# stm32g474.net
KiCad netlist of a schematic drawn in Altium Designer
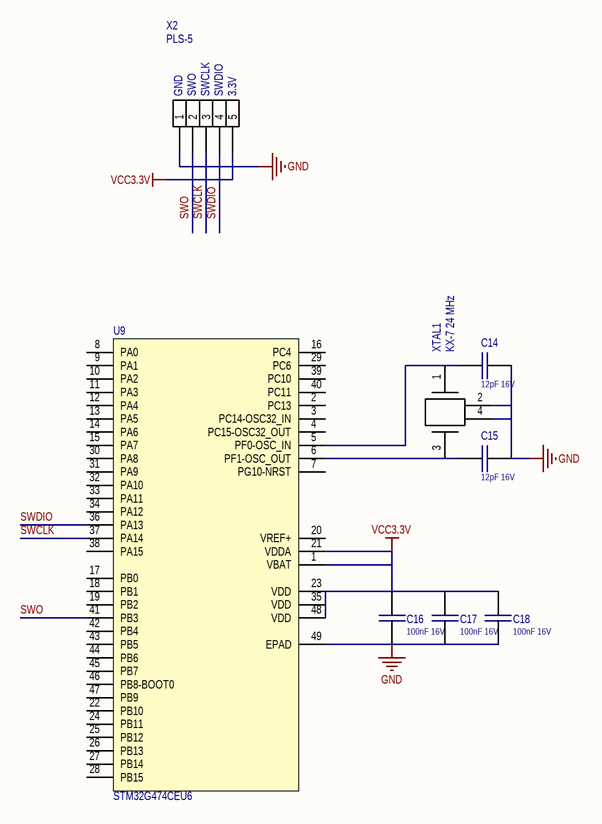
[diagram p0: stm32g474.schdoc]

(export (version "E")
  (design (tool "Eeschema 10.0.6"))
  (components
    (comp (ref "C14")
      (value "12pF 16V")
      (footprint "C_0603")
      (description "Capacitor")
      (libsource (lib "AX_Altium_v2.3") (part "C0603"))
    )
    (comp (ref "C15")
      (value "12pF 16V")
      (footprint "C_0603")
      (description "Capacitor")
      (libsource (lib "AX_Altium_v2.3") (part "C0603"))
    )
    (comp (ref "C16")
      (value "100nF 16V")
      (footprint "C_0603")
      (description "Capacitor")
      (libsource (lib "AX_Altium_v2.3") (part "C0603"))
    )
    (comp (ref "C17")
      (value "100nF 16V")
      (footprint "C_0603")
      (description "Capacitor")
      (libsource (lib "AX_Altium_v2.3") (part "C0603"))
    )
    (comp (ref "C18")
      (value "100nF 16V")
      (footprint "C_0603")
      (description "Capacitor")
      (libsource (lib "AX_Altium_v2.3") (part "C0603"))
    )
    (comp (ref "U9")
      (value "STM32G474CEU6")
      (footprint "STM-UFQFPN48_M")
      (description "MCU")
      (libsource (lib "AX_Altium_v2.3") (part "STM32G474CEU6"))
    )
    (comp (ref "X2")
      (value "PLS-5")
      (footprint "PLS-5-3D")
      (description "Header, 5-Pin")
      (fields (field (name "PUBLISHER") "Altium Limited"))
      (libsource (lib "ConnectorButtonSocetDisplay") (part "PLS2-5"))
    )
    (comp (ref "XTAL1")
      (value "KX-7 24 MHz")
      (footprint "KX - 7")
      (description "Quartz")
      (libsource (lib "AX_Altium_v2.3") (part "KX-7"))
    )
  )
  (nets
    (net (code "1") (name "/SWCLK") (class "Default")
      (node (ref "U9") (pin "37") (pinfunction "PA14_37") (pintype "passive"))
      (node (ref "X2") (pin "3") (pinfunction "3_3") (pintype "passive"))
    )
    (net (code "2") (name "/SWDIO") (class "Default")
      (node (ref "U9") (pin "36") (pinfunction "PA13_36") (pintype "passive"))
      (node (ref "X2") (pin "4") (pinfunction "4_4") (pintype "passive"))
    )
    (net (code "3") (name "/SWO") (class "Default")
      (node (ref "U9") (pin "41") (pinfunction "PB3_41") (pintype "passive"))
      (node (ref "X2") (pin "2") (pinfunction "2_2") (pintype "passive"))
    )
    (net (code "4") (name "GND") (class "Default")
      (node (ref "C14") (pin "2") (pinfunction "2_2") (pintype "passive"))
      (node (ref "C15") (pin "2") (pinfunction "2_2") (pintype "passive"))
      (node (ref "C16") (pin "1") (pinfunction "1_1") (pintype "passive"))
      (node (ref "C17") (pin "1") (pinfunction "1_1") (pintype "passive"))
      (node (ref "C18") (pin "1") (pinfunction "1_1") (pintype "passive"))
      (node (ref "U9") (pin "49") (pinfunction "EPAD_49") (pintype "passive"))
      (node (ref "X2") (pin "1") (pinfunction "1_1") (pintype "passive"))
      (node (ref "XTAL1") (pin "2") (pinfunction "GND_2") (pintype "passive"))
      (node (ref "XTAL1") (pin "4") (pinfunction "5_4") (pintype "passive"))
    )
    (net (code "5") (name "Net-(U9-PF0-OSC_IN)") (class "Default")
      (node (ref "C14") (pin "1") (pinfunction "1_1") (pintype "passive"))
      (node (ref "U9") (pin "5") (pinfunction "PF0-OSC_IN_5") (pintype "passive"))
      (node (ref "XTAL1") (pin "1") (pintype "passive"))
    )
    (net (code "6") (name "Net-(U9-PF1-OSC_OUT)") (class "Default")
      (node (ref "C15") (pin "1") (pinfunction "1_1") (pintype "passive"))
      (node (ref "U9") (pin "6") (pinfunction "PF1-OSC_OUT_6") (pintype "passive"))
      (node (ref "XTAL1") (pin "3") (pintype "passive"))
    )
    (net (code "7") (name "VCC3.3V") (class "Default")
      (node (ref "C16") (pin "2") (pinfunction "2_2") (pintype "passive"))
      (node (ref "C17") (pin "2") (pinfunction "2_2") (pintype "passive"))
      (node (ref "C18") (pin "2") (pinfunction "2_2") (pintype "passive"))
      (node (ref "U9") (pin "1") (pinfunction "VBAT_1") (pintype "passive"))
      (node (ref "U9") (pin "21") (pinfunction "VDDA_21") (pintype "passive"))
      (node (ref "U9") (pin "23") (pinfunction "VDD_23") (pintype "passive"))
      (node (ref "U9") (pin "35") (pinfunction "VDD_35") (pintype "passive"))
      (node (ref "U9") (pin "48") (pinfunction "VDD_48") (pintype "passive"))
      (node (ref "X2") (pin "5") (pinfunction "5_5") (pintype "passive"))
    )
    (net (code "8") (name "unconnected-(U9-PA0-Pad8)") (class "Default")
      (node (ref "U9") (pin "8") (pinfunction "PA0_8") (pintype "passive"))
    )
    (net (code "9") (name "unconnected-(U9-PA1-Pad9)") (class "Default")
      (node (ref "U9") (pin "9") (pinfunction "PA1_9") (pintype "passive"))
    )
    (net (code "10") (name "unconnected-(U9-PA2-Pad10)") (class "Default")
      (node (ref "U9") (pin "10") (pinfunction "PA2_10") (pintype "passive"))
    )
    (net (code "11") (name "unconnected-(U9-PA3-Pad11)") (class "Default")
      (node (ref "U9") (pin "11") (pinfunction "PA3_11") (pintype "passive"))
    )
    (net (code "12") (name "unconnected-(U9-PA4-Pad12)") (class "Default")
      (node (ref "U9") (pin "12") (pinfunction "PA4_12") (pintype "passive"))
    )
    (net (code "13") (name "unconnected-(U9-PA5-Pad13)") (class "Default")
      (node (ref "U9") (pin "13") (pinfunction "PA5_13") (pintype "passive"))
    )
    (net (code "14") (name "unconnected-(U9-PA6-Pad14)") (class "Default")
      (node (ref "U9") (pin "14") (pinfunction "PA6_14") (pintype "passive"))
    )
    (net (code "15") (name "unconnected-(U9-PA7-Pad15)") (class "Default")
      (node (ref "U9") (pin "15") (pinfunction "PA7_15") (pintype "passive"))
    )
    (net (code "16") (name "unconnected-(U9-PA8-Pad30)") (class "Default")
      (node (ref "U9") (pin "30") (pinfunction "PA8_30") (pintype "passive"))
    )
    (net (code "17") (name "unconnected-(U9-PA9-Pad31)") (class "Default")
      (node (ref "U9") (pin "31") (pinfunction "PA9_31") (pintype "passive"))
    )
    (net (code "18") (name "unconnected-(U9-PA10-Pad32)") (class "Default")
      (node (ref "U9") (pin "32") (pinfunction "PA10_32") (pintype "passive"))
    )
    (net (code "19") (name "unconnected-(U9-PA11-Pad33)") (class "Default")
      (node (ref "U9") (pin "33") (pinfunction "PA11_33") (pintype "passive"))
    )
    (net (code "20") (name "unconnected-(U9-PA12-Pad34)") (class "Default")
      (node (ref "U9") (pin "34") (pinfunction "PA12_34") (pintype "passive"))
    )
    (net (code "21") (name "unconnected-(U9-PA15-Pad38)") (class "Default")
      (node (ref "U9") (pin "38") (pinfunction "PA15_38") (pintype "passive"))
    )
    (net (code "22") (name "unconnected-(U9-PB0-Pad17)") (class "Default")
      (node (ref "U9") (pin "17") (pinfunction "PB0_17") (pintype "passive"))
    )
    (net (code "23") (name "unconnected-(U9-PB1-Pad18)") (class "Default")
      (node (ref "U9") (pin "18") (pinfunction "PB1_18") (pintype "passive"))
    )
    (net (code "24") (name "unconnected-(U9-PB2-Pad19)") (class "Default")
      (node (ref "U9") (pin "19") (pinfunction "PB2_19") (pintype "passive"))
    )
    (net (code "25") (name "unconnected-(U9-PB4-Pad42)") (class "Default")
      (node (ref "U9") (pin "42") (pinfunction "PB4_42") (pintype "passive"))
    )
    (net (code "26") (name "unconnected-(U9-PB5-Pad43)") (class "Default")
      (node (ref "U9") (pin "43") (pinfunction "PB5_43") (pintype "passive"))
    )
    (net (code "27") (name "unconnected-(U9-PB6-Pad44)") (class "Default")
      (node (ref "U9") (pin "44") (pinfunction "PB6_44") (pintype "passive"))
    )
    (net (code "28") (name "unconnected-(U9-PB7-Pad45)") (class "Default")
      (node (ref "U9") (pin "45") (pinfunction "PB7_45") (pintype "passive"))
    )
    (net (code "29") (name "unconnected-(U9-PB8-BOOT0-Pad46)") (class "Default")
      (node (ref "U9") (pin "46") (pinfunction "PB8-BOOT0_46") (pintype "passive"))
    )
    (net (code "30") (name "unconnected-(U9-PB9-Pad47)") (class "Default")
      (node (ref "U9") (pin "47") (pinfunction "PB9_47") (pintype "passive"))
    )
    (net (code "31") (name "unconnected-(U9-PB10-Pad22)") (class "Default")
      (node (ref "U9") (pin "22") (pinfunction "PB10_22") (pintype "passive"))
    )
    (net (code "32") (name "unconnected-(U9-PB11-Pad24)") (class "Default")
      (node (ref "U9") (pin "24") (pinfunction "PB11_24") (pintype "passive"))
    )
    (net (code "33") (name "unconnected-(U9-PB12-Pad25)") (class "Default")
      (node (ref "U9") (pin "25") (pinfunction "PB12_25") (pintype "passive"))
    )
    (net (code "34") (name "unconnected-(U9-PB13-Pad26)") (class "Default")
      (node (ref "U9") (pin "26") (pinfunction "PB13_26") (pintype "passive"))
    )
    (net (code "35") (name "unconnected-(U9-PB14-Pad27)") (class "Default")
      (node (ref "U9") (pin "27") (pinfunction "PB14_27") (pintype "passive"))
    )
    (net (code "36") (name "unconnected-(U9-PB15-Pad28)") (class "Default")
      (node (ref "U9") (pin "28") (pinfunction "PB15_28") (pintype "passive"))
    )
    (net (code "37") (name "unconnected-(U9-PC4-Pad16)") (class "Default")
      (node (ref "U9") (pin "16") (pinfunction "PC4_16") (pintype "passive"))
    )
    (net (code "38") (name "unconnected-(U9-PC6-Pad29)") (class "Default")
      (node (ref "U9") (pin "29") (pinfunction "PC6_29") (pintype "passive"))
    )
    (net (code "39") (name "unconnected-(U9-PC10-Pad39)") (class "Default")
      (node (ref "U9") (pin "39") (pinfunction "PC10_39") (pintype "passive"))
    )
    (net (code "40") (name "unconnected-(U9-PC11-Pad40)") (class "Default")
      (node (ref "U9") (pin "40") (pinfunction "PC11_40") (pintype "passive"))
    )
    (net (code "41") (name "unconnected-(U9-PC13-Pad2)") (class "Default")
      (node (ref "U9") (pin "2") (pinfunction "PC13_2") (pintype "passive"))
    )
    (net (code "42") (name "unconnected-(U9-PC14-OSC32_IN-Pad3)") (class "Default")
      (node (ref "U9") (pin "3") (pinfunction "PC14-OSC32_IN_3") (pintype "passive"))
    )
    (net (code "43") (name "unconnected-(U9-PC15-OSC32_OUT-Pad4)") (class "Default")
      (node (ref "U9") (pin "4") (pinfunction "PC15-OSC32_OUT_4") (pintype "passive"))
    )
    (net (code "44") (name "unconnected-(U9-PG10-NRST-Pad7)") (class "Default")
      (node (ref "U9") (pin "7") (pinfunction "PG10-NRST_7") (pintype "passive"))
    )
    (net (code "45") (name "unconnected-(U9-VREF+-Pad20)") (class "Default")
      (node (ref "U9") (pin "20") (pinfunction "VREF+_20") (pintype "passive"))
    )
  )
)
